# CANdiy-Shield_v13.net
KiCad netlist of a schematic drawn in EAGLE
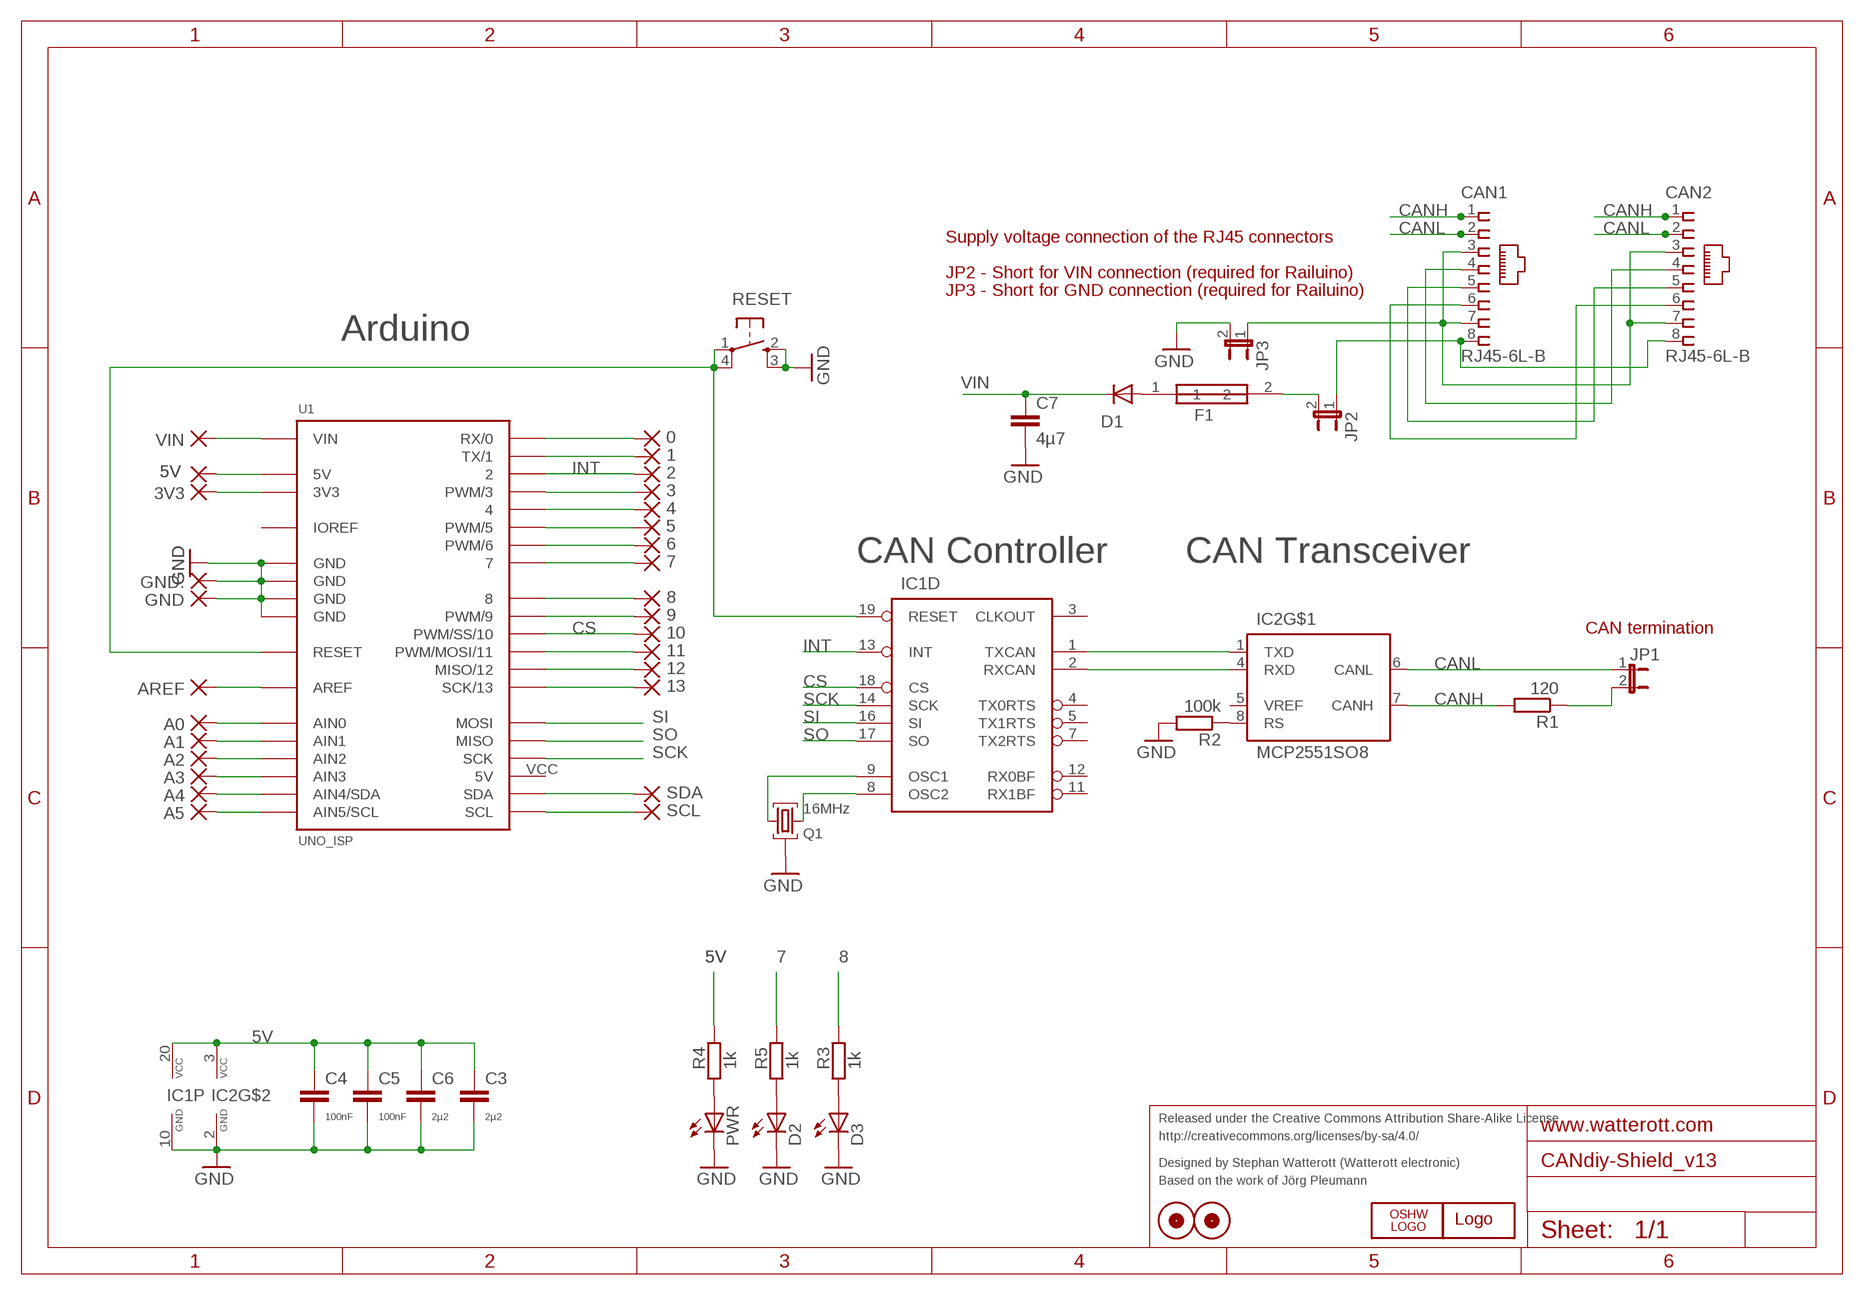
[diagram p0: schematic, sheet 1]

(export (version "E")
  (design (tool "Eeschema 10.0.6"))
  (components
    (comp (ref "0")
      (value "1,6/0,8")
      (footprint "eagle-import:1,6_0,8")
      (libsource (lib "eagle-import") (part "1,6/0,8"))
    )
    (comp (ref "1")
      (value "1,6/0,8")
      (footprint "eagle-import:1,6_0,8")
      (libsource (lib "eagle-import") (part "1,6/0,8"))
    )
    (comp (ref "2")
      (value "1,6/0,8")
      (footprint "eagle-import:1,6_0,8")
      (libsource (lib "eagle-import") (part "1,6/0,8"))
    )
    (comp (ref "3")
      (value "1,6/0,8")
      (footprint "eagle-import:1,6_0,8")
      (libsource (lib "eagle-import") (part "1,6/0,8"))
    )
    (comp (ref "3V3")
      (value "1,6/0,8")
      (footprint "eagle-import:1,6_0,8")
      (libsource (lib "eagle-import") (part "1,6/0,8"))
    )
    (comp (ref "4")
      (value "1,6/0,8")
      (footprint "eagle-import:1,6_0,8")
      (libsource (lib "eagle-import") (part "1,6/0,8"))
    )
    (comp (ref "5")
      (value "1,6/0,8")
      (footprint "eagle-import:1,6_0,8")
      (libsource (lib "eagle-import") (part "1,6/0,8"))
    )
    (comp (ref "5V")
      (value "1,6/0,8")
      (footprint "eagle-import:1,6_0,8")
      (libsource (lib "eagle-import") (part "1,6/0,8"))
    )
    (comp (ref "6")
      (value "1,6/0,8")
      (footprint "eagle-import:1,6_0,8")
      (libsource (lib "eagle-import") (part "1,6/0,8"))
    )
    (comp (ref "7")
      (value "1,6/0,8")
      (footprint "eagle-import:1,6_0,8")
      (libsource (lib "eagle-import") (part "1,6/0,8"))
    )
    (comp (ref "8")
      (value "1,6/0,8")
      (footprint "eagle-import:1,6_0,8")
      (libsource (lib "eagle-import") (part "1,6/0,8"))
    )
    (comp (ref "9")
      (value "1,6/0,8")
      (footprint "eagle-import:1,6_0,8")
      (libsource (lib "eagle-import") (part "1,6/0,8"))
    )
    (comp (ref "10")
      (value "1,6/0,8")
      (footprint "eagle-import:1,6_0,8")
      (libsource (lib "eagle-import") (part "1,6/0,8"))
    )
    (comp (ref "11")
      (value "1,6/0,8")
      (footprint "eagle-import:1,6_0,8")
      (libsource (lib "eagle-import") (part "1,6/0,8"))
    )
    (comp (ref "12")
      (value "1,6/0,8")
      (footprint "eagle-import:1,6_0,8")
      (libsource (lib "eagle-import") (part "1,6/0,8"))
    )
    (comp (ref "13")
      (value "1,6/0,8")
      (footprint "eagle-import:1,6_0,8")
      (libsource (lib "eagle-import") (part "1,6/0,8"))
    )
    (comp (ref "A0")
      (value "1,6/0,8")
      (footprint "eagle-import:1,6_0,8")
      (libsource (lib "eagle-import") (part "1,6/0,8"))
    )
    (comp (ref "A1")
      (value "1,6/0,8")
      (footprint "eagle-import:1,6_0,8")
      (libsource (lib "eagle-import") (part "1,6/0,8"))
    )
    (comp (ref "A2")
      (value "1,6/0,8")
      (footprint "eagle-import:1,6_0,8")
      (libsource (lib "eagle-import") (part "1,6/0,8"))
    )
    (comp (ref "A3")
      (value "1,6/0,8")
      (footprint "eagle-import:1,6_0,8")
      (libsource (lib "eagle-import") (part "1,6/0,8"))
    )
    (comp (ref "A4")
      (value "1,6/0,8")
      (footprint "eagle-import:1,6_0,8")
      (libsource (lib "eagle-import") (part "1,6/0,8"))
    )
    (comp (ref "A5")
      (value "1,6/0,8")
      (footprint "eagle-import:1,6_0,8")
      (libsource (lib "eagle-import") (part "1,6/0,8"))
    )
    (comp (ref "AREF")
      (value "1,6/0,8")
      (footprint "eagle-import:1,6_0,8")
      (libsource (lib "eagle-import") (part "1,6/0,8"))
    )
    (comp (ref "C3")
      (value "2µ2")
      (footprint "eagle-import:C0603")
      (libsource (lib "eagle-import") (part "C-EUC0603"))
    )
    (comp (ref "C4")
      (value "100nF")
      (footprint "eagle-import:C0603")
      (libsource (lib "eagle-import") (part "C-EUC0603"))
    )
    (comp (ref "C5")
      (value "100nF")
      (footprint "eagle-import:C0603")
      (libsource (lib "eagle-import") (part "C-EUC0603"))
    )
    (comp (ref "C6")
      (value "2µ2")
      (footprint "eagle-import:C0603")
      (libsource (lib "eagle-import") (part "C-EUC0603"))
    )
    (comp (ref "C7")
      (value "4µ7")
      (footprint "eagle-import:C1206")
      (libsource (lib "eagle-import") (part "C-EUC1206"))
    )
    (comp (ref "CAN1")
      (value "RJ45-6L-B")
      (footprint "eagle-import:RJ45-NO-SHIELD")
      (libsource (lib "eagle-import") (part "RJ45-6L-B"))
    )
    (comp (ref "CAN2")
      (value "RJ45-6L-B")
      (footprint "eagle-import:RJ45-NO-SHIELD")
      (libsource (lib "eagle-import") (part "RJ45-6L-B"))
    )
    (comp (ref "D1")
      (value "CGRM4001-G")
      (footprint "eagle-import:SOD-123_MINI-SMA")
      (libsource (lib "eagle-import") (part "CGRM400-G1"))
    )
    (comp (ref "D2")
      (value "LEDCHIPLED_0603")
      (footprint "eagle-import:CHIPLED_0603")
      (libsource (lib "eagle-import") (part "LEDCHIPLED_0603"))
    )
    (comp (ref "D3")
      (value "LEDCHIPLED_0603")
      (footprint "eagle-import:CHIPLED_0603")
      (libsource (lib "eagle-import") (part "LEDCHIPLED_0603"))
    )
    (comp (ref "F1")
      (value "F1")
      (footprint "eagle-import:L1812")
      (libsource (lib "eagle-import") (part "FUSE1812"))
    )
    (comp (ref "GND")
      (value "1,6/0,8")
      (footprint "eagle-import:1,6_0,8")
      (libsource (lib "eagle-import") (part "1,6/0,8"))
    )
    (comp (ref "GND.")
      (value "1,6/0,8")
      (footprint "eagle-import:1,6_0,8")
      (libsource (lib "eagle-import") (part "1,6/0,8"))
    )
    (comp (ref "IC1")
      (value "MCP2515ST")
      (footprint "eagle-import:TSSOP20")
      (libsource (lib "eagle-import") (part "MCP2515ST"))
    )
    (comp (ref "IC2")
      (value "MCP2551SO8")
      (footprint "eagle-import:SO08")
      (libsource (lib "eagle-import") (part "MCP2551SO8"))
    )
    (comp (ref "JP1")
      (value "JP1E")
      (footprint "eagle-import:JP1")
      (libsource (lib "eagle-import") (part "JP1E"))
    )
    (comp (ref "JP2")
      (value "JP1E")
      (footprint "eagle-import:JP1")
      (libsource (lib "eagle-import") (part "JP1E"))
    )
    (comp (ref "JP3")
      (value "JP1E")
      (footprint "eagle-import:JP1")
      (libsource (lib "eagle-import") (part "JP1E"))
    )
    (comp (ref "LOGO2")
      (value "OSHW_LOGO_6MILX0100-NT")
      (footprint "eagle-import:OSHW_6X100_NOTEXT")
      (libsource (lib "eagle-import") (part "OSHW_LOGO_6MILX0100-NT"))
    )
    (comp (ref "PWR")
      (value "LEDCHIPLED_0603")
      (footprint "eagle-import:CHIPLED_0603")
      (libsource (lib "eagle-import") (part "LEDCHIPLED_0603"))
    )
    (comp (ref "Q1")
      (value "16MHz")
      (footprint "eagle-import:SMD_OSC_35X15")
      (libsource (lib "eagle-import") (part "SMD_OSC2"))
    )
    (comp (ref "R1")
      (value "120")
      (footprint "eagle-import:R0603")
      (libsource (lib "eagle-import") (part "resistor_R-EU_R0603"))
    )
    (comp (ref "R2")
      (value "100k")
      (footprint "eagle-import:R0603")
      (libsource (lib "eagle-import") (part "resistor_R-EU_R0603"))
    )
    (comp (ref "R3")
      (value "1k")
      (footprint "eagle-import:R0603")
      (libsource (lib "eagle-import") (part "R-EU_R0603"))
    )
    (comp (ref "R4")
      (value "1k")
      (footprint "eagle-import:R0603")
      (libsource (lib "eagle-import") (part "R-EU_R0603"))
    )
    (comp (ref "R5")
      (value "1k")
      (footprint "eagle-import:R0603")
      (libsource (lib "eagle-import") (part "R-EU_R0603"))
    )
    (comp (ref "RESET")
      (value "SW_SMDS")
      (footprint "eagle-import:SW_SMD4")
      (libsource (lib "eagle-import") (part "SW_SMDS"))
    )
    (comp (ref "SCL")
      (value "1,6/0,8")
      (footprint "eagle-import:1,6_0,8")
      (libsource (lib "eagle-import") (part "1,6/0,8"))
    )
    (comp (ref "SDA")
      (value "1,6/0,8")
      (footprint "eagle-import:1,6_0,8")
      (libsource (lib "eagle-import") (part "1,6/0,8"))
    )
    (comp (ref "U$1")
      (value "WE-LOGO")
      (footprint "eagle-import:WE-LOGO")
      (libsource (lib "eagle-import") (part "WE-LOGO"))
    )
    (comp (ref "U1")
      (value "UNO_ISP")
      (footprint "eagle-import:UNO_ISP")
      (libsource (lib "eagle-import") (part "UNO_ISP"))
    )
    (comp (ref "VIN")
      (value "1,6/0,8")
      (footprint "eagle-import:1,6_0,8")
      (libsource (lib "eagle-import") (part "1,6/0,8"))
    )
    (comp (ref "X_1")
      (value "PASS_1MM")
      (footprint "eagle-import:ROUND_1MM")
      (libsource (lib "eagle-import") (part "PASS_1MM"))
    )
    (comp (ref "X_2")
      (value "PASS_1MM")
      (footprint "eagle-import:ROUND_1MM")
      (libsource (lib "eagle-import") (part "PASS_1MM"))
    )
  )
  (nets
    (net (code "1") (name "/5V") (class "Default")
      (node (ref "5V") (pin "1") (pinfunction "P_1") (pintype "passive"))
      (node (ref "C3") (pin "1") (pinfunction "1_1") (pintype "passive"))
      (node (ref "C4") (pin "1") (pinfunction "1_1") (pintype "passive"))
      (node (ref "C5") (pin "1") (pinfunction "1_1") (pintype "passive"))
      (node (ref "C6") (pin "1") (pinfunction "1_1") (pintype "passive"))
      (node (ref "IC1") (pin "20") (pinfunction "VCC_20") (pintype "power_in"))
      (node (ref "IC2") (pin "3") (pinfunction "VCC_3") (pintype "power_in"))
      (node (ref "R4") (pin "1") (pinfunction "1_1") (pintype "passive"))
      (node (ref "U1") (pin "5V") (pinfunction "5V_5V") (pintype "power_in"))
    )
    (net (code "2") (name "/7") (class "Default")
      (node (ref "7") (pin "1") (pinfunction "P_1") (pintype "passive"))
      (node (ref "R5") (pin "1") (pinfunction "1_1") (pintype "passive"))
      (node (ref "U1") (pin "7") (pinfunction "7_7") (pintype "bidirectional"))
    )
    (net (code "3") (name "/8") (class "Default")
      (node (ref "8") (pin "1") (pinfunction "P_1") (pintype "passive"))
      (node (ref "R3") (pin "1") (pinfunction "1_1") (pintype "passive"))
      (node (ref "U1") (pin "8") (pinfunction "8_8") (pintype "bidirectional"))
    )
    (net (code "4") (name "/CANH") (class "Default")
      (node (ref "CAN1") (pin "1") (pinfunction "1_1") (pintype "passive"))
      (node (ref "CAN2") (pin "1") (pinfunction "1_1") (pintype "passive"))
      (node (ref "IC2") (pin "7") (pinfunction "CANH_7") (pintype "bidirectional"))
      (node (ref "R1") (pin "2") (pinfunction "2_2") (pintype "passive"))
    )
    (net (code "5") (name "/CANL") (class "Default")
      (node (ref "CAN1") (pin "2") (pinfunction "2_2") (pintype "passive"))
      (node (ref "CAN2") (pin "2") (pinfunction "2_2") (pintype "passive"))
      (node (ref "IC2") (pin "6") (pinfunction "CANL_6") (pintype "bidirectional"))
      (node (ref "JP1") (pin "1") (pinfunction "1_1") (pintype "passive"))
    )
    (net (code "6") (name "/CS") (class "Default")
      (node (ref "10") (pin "1") (pinfunction "P_1") (pintype "passive"))
      (node (ref "IC1") (pin "18") (pinfunction "CS_18") (pintype "input"))
      (node (ref "U1") (pin "10") (pinfunction "PWM/SS/10_10") (pintype "bidirectional"))
    )
    (net (code "7") (name "/INT") (class "Default")
      (node (ref "2") (pin "1") (pinfunction "P_1") (pintype "passive"))
      (node (ref "IC1") (pin "13") (pinfunction "INT_13") (pintype "output"))
      (node (ref "U1") (pin "2") (pinfunction "2_2") (pintype "bidirectional"))
    )
    (net (code "8") (name "/IOREF") (class "Default")
      (node (ref "U1") (pin "IOREF") (pinfunction "IOREF_IOREF") (pintype "power_in"))
    )
    (net (code "9") (name "/SCK") (class "Default")
      (node (ref "IC1") (pin "14") (pinfunction "SCK_14") (pintype "input"))
      (node (ref "U1") (pin "SCK") (pinfunction "SCK_SCK") (pintype "bidirectional"))
    )
    (net (code "10") (name "/SI") (class "Default")
      (node (ref "IC1") (pin "16") (pinfunction "SI_16") (pintype "input"))
      (node (ref "U1") (pin "MOSI") (pinfunction "MOSI_MOSI") (pintype "bidirectional"))
    )
    (net (code "11") (name "/SO") (class "Default")
      (node (ref "IC1") (pin "17") (pinfunction "SO_17") (pintype "output"))
      (node (ref "U1") (pin "MISO") (pinfunction "MISO_MISO") (pintype "bidirectional"))
    )
    (net (code "12") (name "/VIN") (class "Default")
      (node (ref "C7") (pin "1") (pinfunction "1_1") (pintype "passive"))
      (node (ref "D1") (pin "C") (pinfunction "C_C") (pintype "passive"))
      (node (ref "U1") (pin "VIN") (pinfunction "VIN_VIN") (pintype "power_in"))
      (node (ref "VIN") (pin "1") (pinfunction "P_1") (pintype "passive"))
    )
    (net (code "13") (name "GND") (class "Default")
      (node (ref "C3") (pin "2") (pinfunction "2_2") (pintype "passive"))
      (node (ref "C4") (pin "2") (pinfunction "2_2") (pintype "passive"))
      (node (ref "C5") (pin "2") (pinfunction "2_2") (pintype "passive"))
      (node (ref "C6") (pin "2") (pinfunction "2_2") (pintype "passive"))
      (node (ref "C7") (pin "2") (pinfunction "2_2") (pintype "passive"))
      (node (ref "D2") (pin "C") (pinfunction "C_C") (pintype "passive"))
      (node (ref "D3") (pin "C") (pinfunction "C_C") (pintype "passive"))
      (node (ref "GND") (pin "1") (pinfunction "P_1") (pintype "passive"))
      (node (ref "GND.") (pin "1") (pinfunction "P_1") (pintype "passive"))
      (node (ref "IC1") (pin "10") (pinfunction "GND_10") (pintype "power_in"))
      (node (ref "IC2") (pin "2") (pinfunction "GND_2") (pintype "power_in"))
      (node (ref "JP3") (pin "2") (pinfunction "2_2") (pintype "passive"))
      (node (ref "PWR") (pin "C") (pinfunction "C_C") (pintype "passive"))
      (node (ref "Q1") (pin "GND") (pinfunction "GND_GND") (pintype "passive"))
      (node (ref "R2") (pin "2") (pinfunction "2_2") (pintype "passive"))
      (node (ref "RESET") (pin "2") (pinfunction "S_2") (pintype "passive"))
      (node (ref "RESET") (pin "3") (pinfunction "S1_3") (pintype "passive"))
      (node (ref "U1") (pin "GND@1") (pinfunction "GND_GND@1") (pintype "power_in"))
      (node (ref "U1") (pin "GND@2") (pinfunction "GND_GND@2") (pintype "power_in"))
      (node (ref "U1") (pin "GND@3") (pinfunction "GND_GND@3") (pintype "power_in"))
      (node (ref "U1") (pin "GND@4") (pinfunction "GND_GND@4") (pintype "power_in"))
    )
    (net (code "14") (name "Net-(0-P)") (class "Default")
      (node (ref "0") (pin "1") (pinfunction "P_1") (pintype "passive"))
      (node (ref "U1") (pin "0") (pinfunction "RX/0_0") (pintype "bidirectional"))
    )
    (net (code "15") (name "Net-(1-P)") (class "Default")
      (node (ref "1") (pin "1") (pinfunction "P_1") (pintype "passive"))
      (node (ref "U1") (pin "1") (pinfunction "TX/1_1") (pintype "bidirectional"))
    )
    (net (code "16") (name "Net-(3-P)") (class "Default")
      (node (ref "3") (pin "1") (pinfunction "P_1") (pintype "passive"))
      (node (ref "U1") (pin "3") (pinfunction "PWM/3_3") (pintype "bidirectional"))
    )
    (net (code "17") (name "Net-(3V3-P)") (class "Default")
      (node (ref "3V3") (pin "1") (pinfunction "P_1") (pintype "passive"))
      (node (ref "U1") (pin "3V3") (pinfunction "3V3_3V3") (pintype "power_in"))
    )
    (net (code "18") (name "Net-(4-P)") (class "Default")
      (node (ref "4") (pin "1") (pinfunction "P_1") (pintype "passive"))
      (node (ref "U1") (pin "4") (pinfunction "4_4") (pintype "bidirectional"))
    )
    (net (code "19") (name "Net-(5-P)") (class "Default")
      (node (ref "5") (pin "1") (pinfunction "P_1") (pintype "passive"))
      (node (ref "U1") (pin "5") (pinfunction "PWM/5_5") (pintype "bidirectional"))
    )
    (net (code "20") (name "Net-(6-P)") (class "Default")
      (node (ref "6") (pin "1") (pinfunction "P_1") (pintype "passive"))
      (node (ref "U1") (pin "6") (pinfunction "PWM/6_6") (pintype "bidirectional"))
    )
    (net (code "21") (name "Net-(9-P)") (class "Default")
      (node (ref "9") (pin "1") (pinfunction "P_1") (pintype "passive"))
      (node (ref "U1") (pin "9") (pinfunction "PWM/9_9") (pintype "bidirectional"))
    )
    (net (code "22") (name "Net-(11-P)") (class "Default")
      (node (ref "11") (pin "1") (pinfunction "P_1") (pintype "passive"))
      (node (ref "U1") (pin "11") (pinfunction "PWM/MOSI/11_11") (pintype "bidirectional"))
    )
    (net (code "23") (name "Net-(12-P)") (class "Default")
      (node (ref "12") (pin "1") (pinfunction "P_1") (pintype "passive"))
      (node (ref "U1") (pin "12") (pinfunction "MISO/12_12") (pintype "bidirectional"))
    )
    (net (code "24") (name "Net-(13-P)") (class "Default")
      (node (ref "13") (pin "1") (pinfunction "P_1") (pintype "passive"))
      (node (ref "U1") (pin "13") (pinfunction "SCK/13_13") (pintype "bidirectional"))
    )
    (net (code "25") (name "Net-(A0-P)") (class "Default")
      (node (ref "A0") (pin "1") (pinfunction "P_1") (pintype "passive"))
      (node (ref "U1") (pin "AIN0") (pinfunction "AIN0_AIN0") (pintype "bidirectional"))
    )
    (net (code "26") (name "Net-(A1-P)") (class "Default")
      (node (ref "A1") (pin "1") (pinfunction "P_1") (pintype "passive"))
      (node (ref "U1") (pin "AIN1") (pinfunction "AIN1_AIN1") (pintype "bidirectional"))
    )
    (net (code "27") (name "Net-(A2-P)") (class "Default")
      (node (ref "A2") (pin "1") (pinfunction "P_1") (pintype "passive"))
      (node (ref "U1") (pin "AIN2") (pinfunction "AIN2_AIN2") (pintype "bidirectional"))
    )
    (net (code "28") (name "Net-(A3-P)") (class "Default")
      (node (ref "A3") (pin "1") (pinfunction "P_1") (pintype "passive"))
      (node (ref "U1") (pin "AIN3") (pinfunction "AIN3_AIN3") (pintype "bidirectional"))
    )
    (net (code "29") (name "Net-(A4-P)") (class "Default")
      (node (ref "A4") (pin "1") (pinfunction "P_1") (pintype "passive"))
      (node (ref "U1") (pin "AIN4") (pinfunction "AIN4/SDA_AIN4") (pintype "bidirectional"))
    )
    (net (code "30") (name "Net-(A5-P)") (class "Default")
      (node (ref "A5") (pin "1") (pinfunction "P_1") (pintype "passive"))
      (node (ref "U1") (pin "AIN5") (pinfunction "AIN5/SCL_AIN5") (pintype "bidirectional"))
    )
    (net (code "31") (name "Net-(AREF-P)") (class "Default")
      (node (ref "AREF") (pin "1") (pinfunction "P_1") (pintype "passive"))
      (node (ref "U1") (pin "AREF") (pinfunction "AREF_AREF") (pintype "power_in"))
    )
    (net (code "32") (name "Net-(CAN1-Pad3)") (class "Default")
      (node (ref "CAN1") (pin "3") (pinfunction "3_3") (pintype "passive"))
      (node (ref "CAN1") (pin "7") (pinfunction "7_7") (pintype "passive"))
      (node (ref "CAN2") (pin "3") (pinfunction "3_3") (pintype "passive"))
      (node (ref "CAN2") (pin "7") (pinfunction "7_7") (pintype "passive"))
      (node (ref "JP3") (pin "1") (pinfunction "1_1") (pintype "passive"))
    )
    (net (code "33") (name "Net-(CAN1-Pad4)") (class "Default")
      (node (ref "CAN1") (pin "4") (pinfunction "4_4") (pintype "passive"))
      (node (ref "CAN2") (pin "4") (pinfunction "4_4") (pintype "passive"))
    )
    (net (code "34") (name "Net-(CAN1-Pad5)") (class "Default")
      (node (ref "CAN1") (pin "5") (pinfunction "5_5") (pintype "passive"))
      (node (ref "CAN2") (pin "5") (pinfunction "5_5") (pintype "passive"))
    )
    (net (code "35") (name "Net-(CAN1-Pad6)") (class "Default")
      (node (ref "CAN1") (pin "6") (pinfunction "6_6") (pintype "passive"))
      (node (ref "CAN2") (pin "6") (pinfunction "6_6") (pintype "passive"))
    )
    (net (code "36") (name "Net-(CAN1-Pad8)") (class "Default")
      (node (ref "CAN1") (pin "8") (pinfunction "8_8") (pintype "passive"))
      (node (ref "CAN2") (pin "8") (pinfunction "8_8") (pintype "passive"))
      (node (ref "JP2") (pin "1") (pinfunction "1_1") (pintype "passive"))
    )
    (net (code "37") (name "Net-(D1-PadA)") (class "Default")
      (node (ref "D1") (pin "A") (pinfunction "A_A") (pintype "passive"))
      (node (ref "F1") (pin "1") (pinfunction "1_1") (pintype "bidirectional"))
    )
    (net (code "38") (name "Net-(D2-PadA)") (class "Default")
      (node (ref "D2") (pin "A") (pinfunction "A_A") (pintype "passive"))
      (node (ref "R5") (pin "2") (pinfunction "2_2") (pintype "passive"))
    )
    (net (code "39") (name "Net-(D3-PadA)") (class "Default")
      (node (ref "D3") (pin "A") (pinfunction "A_A") (pintype "passive"))
      (node (ref "R3") (pin "2") (pinfunction "2_2") (pintype "passive"))
    )
    (net (code "40") (name "Net-(F1-Pad2)") (class "Default")
      (node (ref "F1") (pin "2") (pinfunction "2_2") (pintype "bidirectional"))
      (node (ref "JP2") (pin "2") (pinfunction "2_2") (pintype "passive"))
    )
    (net (code "41") (name "Net-(IC1A-OSC1)") (class "Default")
      (node (ref "IC1") (pin "9") (pinfunction "OSC1_9") (pintype "input"))
      (node (ref "Q1") (pin "1") (pinfunction "1_1") (pintype "passive"))
    )
    (net (code "42") (name "Net-(IC1A-OSC2)") (class "Default")
      (node (ref "IC1") (pin "8") (pinfunction "OSC2_8") (pintype "input"))
      (node (ref "Q1") (pin "2") (pinfunction "2_2") (pintype "passive"))
    )
    (net (code "43") (name "Net-(IC1A-RESET)") (class "Default")
      (node (ref "IC1") (pin "19") (pinfunction "RESET_19") (pintype "input"))
      (node (ref "RESET") (pin "1") (pinfunction "P_1") (pintype "passive"))
      (node (ref "RESET") (pin "4") (pinfunction "P1_4") (pintype "passive"))
      (node (ref "U1") (pin "RST") (pinfunction "RESET_RST") (pintype "bidirectional"))
    )
    (net (code "44") (name "Net-(IC1A-RXCAN)") (class "Default")
      (node (ref "IC1") (pin "2") (pinfunction "RXCAN_2") (pintype "input"))
      (node (ref "IC2") (pin "4") (pinfunction "RXD_4") (pintype "bidirectional"))
    )
    (net (code "45") (name "Net-(IC1A-TXCAN)") (class "Default")
      (node (ref "IC1") (pin "1") (pinfunction "TXCAN_1") (pintype "output"))
      (node (ref "IC2") (pin "1") (pinfunction "TXD_1") (pintype "bidirectional"))
    )
    (net (code "46") (name "Net-(IC2A-RS)") (class "Default")
      (node (ref "IC2") (pin "8") (pinfunction "RS_8") (pintype "bidirectional"))
      (node (ref "R2") (pin "1") (pinfunction "1_1") (pintype "passive"))
    )
    (net (code "47") (name "Net-(JP1-Pad2)") (class "Default")
      (node (ref "JP1") (pin "2") (pinfunction "2_2") (pintype "passive"))
      (node (ref "R1") (pin "1") (pinfunction "1_1") (pintype "passive"))
    )
    (net (code "48") (name "Net-(PWR-PadA)") (class "Default")
      (node (ref "PWR") (pin "A") (pinfunction "A_A") (pintype "passive"))
      (node (ref "R4") (pin "2") (pinfunction "2_2") (pintype "passive"))
    )
    (net (code "49") (name "Net-(SCL-P)") (class "Default")
      (node (ref "SCL") (pin "1") (pinfunction "P_1") (pintype "passive"))
      (node (ref "U1") (pin "SCL") (pinfunction "SCL_SCL") (pintype "bidirectional"))
    )
    (net (code "50") (name "Net-(SDA-P)") (class "Default")
      (node (ref "SDA") (pin "1") (pinfunction "P_1") (pintype "passive"))
      (node (ref "U1") (pin "SDA") (pinfunction "SDA_SDA") (pintype "bidirectional"))
    )
    (net (code "51") (name "unconnected-(IC1A-CLKOUT-Pad3)") (class "Default")
      (node (ref "IC1") (pin "3") (pinfunction "CLKOUT_3") (pintype "output"))
    )
    (net (code "52") (name "unconnected-(IC1A-RX0BF-Pad12)") (class "Default")
      (node (ref "IC1") (pin "12") (pinfunction "RX0BF_12") (pintype "output"))
    )
    (net (code "53") (name "unconnected-(IC1A-RX1BF-Pad11)") (class "Default")
      (node (ref "IC1") (pin "11") (pinfunction "RX1BF_11") (pintype "output"))
    )
    (net (code "54") (name "unconnected-(IC1A-TX0RTS-Pad4)") (class "Default")
      (node (ref "IC1") (pin "4") (pinfunction "TX0RTS_4") (pintype "input"))
    )
    (net (code "55") (name "unconnected-(IC1A-TX1RTS-Pad5)") (class "Default")
      (node (ref "IC1") (pin "5") (pinfunction "TX1RTS_5") (pintype "input"))
    )
    (net (code "56") (name "unconnected-(IC1A-TX2RTS-Pad7)") (class "Default")
      (node (ref "IC1") (pin "7") (pinfunction "TX2RTS_7") (pintype "input"))
    )
    (net (code "57") (name "unconnected-(IC2A-VREF-Pad5)") (class "Default")
      (node (ref "IC2") (pin "5") (pinfunction "VREF_5") (pintype "bidirectional"))
    )
    (net (code "58") (name "unconnected-(U1-5V-PadVCC)") (class "Default")
      (node (ref "U1") (pin "VCC") (pinfunction "5V_VCC") (pintype "bidirectional"))
    )
  )
)
